# module.net
KiCad netlist of a schematic drawn in EAGLE
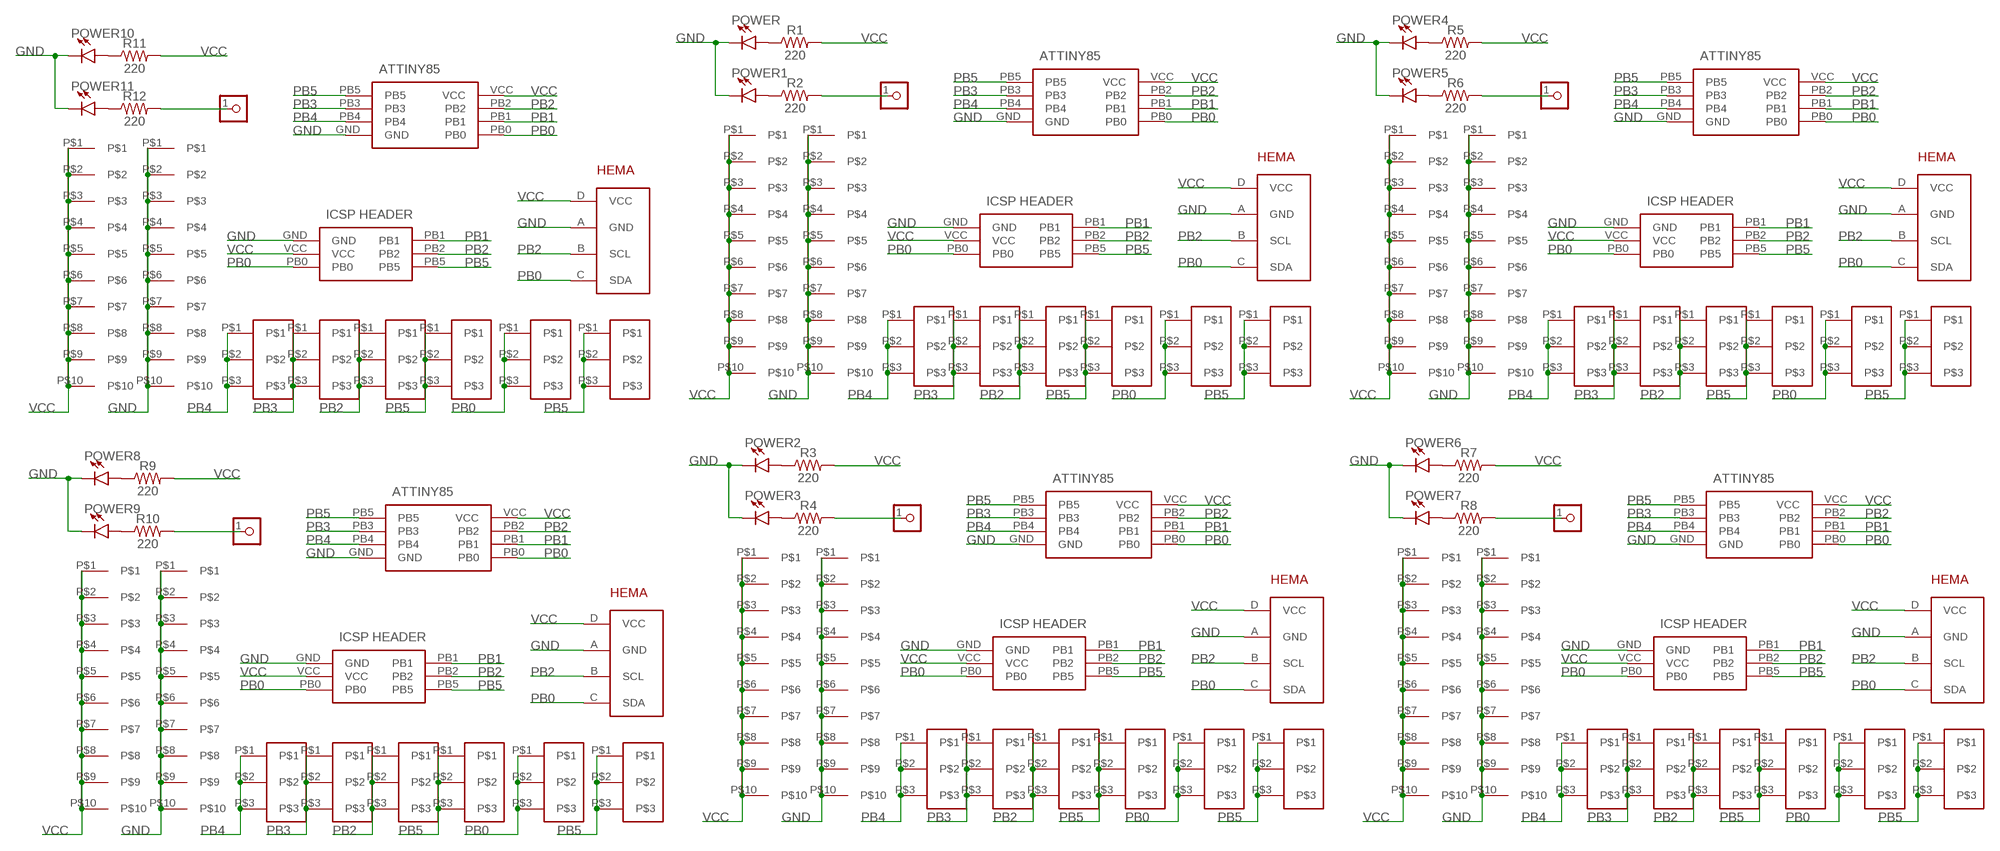
[diagram p0: schematic, sheet 1]

(export (version "E")
  (design (tool "Eeschema 10.0.6"))
  (components
    (comp (ref "0")
      (value "3X-PADS-CONNECTED")
      (footprint "eagle-import:3X-PADS")
      (libsource (lib "eagle-import") (part "3X-PADS-CONNECTED"))
    )
    (comp (ref "1")
      (value "3X-PADS-CONNECTED")
      (footprint "eagle-import:3X-PADS")
      (libsource (lib "eagle-import") (part "3X-PADS-CONNECTED"))
    )
    (comp (ref "2")
      (value "3X-PADS-CONNECTED")
      (footprint "eagle-import:3X-PADS")
      (libsource (lib "eagle-import") (part "3X-PADS-CONNECTED"))
    )
    (comp (ref "3")
      (value "3X-PADS-CONNECTED")
      (footprint "eagle-import:3X-PADS")
      (libsource (lib "eagle-import") (part "3X-PADS-CONNECTED"))
    )
    (comp (ref "4")
      (value "3X-PADS-CONNECTED")
      (footprint "eagle-import:3X-PADS")
      (libsource (lib "eagle-import") (part "3X-PADS-CONNECTED"))
    )
    (comp (ref "5")
      (value "3X-PADS-CONNECTED")
      (footprint "eagle-import:3X-PADS")
      (libsource (lib "eagle-import") (part "3X-PADS-CONNECTED"))
    )
    (comp (ref "6")
      (value "3X-PADS-CONNECTED")
      (footprint "eagle-import:3X-PADS")
      (libsource (lib "eagle-import") (part "3X-PADS-CONNECTED"))
    )
    (comp (ref "7")
      (value "3X-PADS-CONNECTED")
      (footprint "eagle-import:3X-PADS")
      (libsource (lib "eagle-import") (part "3X-PADS-CONNECTED"))
    )
    (comp (ref "8")
      (value "3X-PADS-CONNECTED")
      (footprint "eagle-import:3X-PADS")
      (libsource (lib "eagle-import") (part "3X-PADS-CONNECTED"))
    )
    (comp (ref "9")
      (value "3X-PADS-CONNECTED")
      (footprint "eagle-import:3X-PADS")
      (libsource (lib "eagle-import") (part "3X-PADS-CONNECTED"))
    )
    (comp (ref "10")
      (value "3X-PADS-CONNECTED")
      (footprint "eagle-import:3X-PADS")
      (libsource (lib "eagle-import") (part "3X-PADS-CONNECTED"))
    )
    (comp (ref "11")
      (value "3X-PADS-CONNECTED")
      (footprint "eagle-import:3X-PADS")
      (libsource (lib "eagle-import") (part "3X-PADS-CONNECTED"))
    )
    (comp (ref "12")
      (value "3X-PADS-CONNECTED")
      (footprint "eagle-import:3X-PADS")
      (libsource (lib "eagle-import") (part "3X-PADS-CONNECTED"))
    )
    (comp (ref "13")
      (value "3X-PADS-CONNECTED")
      (footprint "eagle-import:3X-PADS")
      (libsource (lib "eagle-import") (part "3X-PADS-CONNECTED"))
    )
    (comp (ref "14")
      (value "3X-PADS-CONNECTED")
      (footprint "eagle-import:3X-PADS")
      (libsource (lib "eagle-import") (part "3X-PADS-CONNECTED"))
    )
    (comp (ref "15")
      (value "3X-PADS-CONNECTED")
      (footprint "eagle-import:3X-PADS")
      (libsource (lib "eagle-import") (part "3X-PADS-CONNECTED"))
    )
    (comp (ref "16")
      (value "3X-PADS-CONNECTED")
      (footprint "eagle-import:3X-PADS")
      (libsource (lib "eagle-import") (part "3X-PADS-CONNECTED"))
    )
    (comp (ref "17")
      (value "3X-PADS-CONNECTED")
      (footprint "eagle-import:3X-PADS")
      (libsource (lib "eagle-import") (part "3X-PADS-CONNECTED"))
    )
    (comp (ref "18")
      (value "3X-PADS-CONNECTED")
      (footprint "eagle-import:3X-PADS")
      (libsource (lib "eagle-import") (part "3X-PADS-CONNECTED"))
    )
    (comp (ref "19")
      (value "3X-PADS-CONNECTED")
      (footprint "eagle-import:3X-PADS")
      (libsource (lib "eagle-import") (part "3X-PADS-CONNECTED"))
    )
    (comp (ref "20")
      (value "3X-PADS-CONNECTED")
      (footprint "eagle-import:3X-PADS")
      (libsource (lib "eagle-import") (part "3X-PADS-CONNECTED"))
    )
    (comp (ref "21")
      (value "3X-PADS-CONNECTED")
      (footprint "eagle-import:3X-PADS")
      (libsource (lib "eagle-import") (part "3X-PADS-CONNECTED"))
    )
    (comp (ref "22")
      (value "3X-PADS-CONNECTED")
      (footprint "eagle-import:3X-PADS")
      (libsource (lib "eagle-import") (part "3X-PADS-CONNECTED"))
    )
    (comp (ref "23")
      (value "3X-PADS-CONNECTED")
      (footprint "eagle-import:3X-PADS")
      (libsource (lib "eagle-import") (part "3X-PADS-CONNECTED"))
    )
    (comp (ref "24")
      (value "3X-PADS-CONNECTED")
      (footprint "eagle-import:3X-PADS")
      (libsource (lib "eagle-import") (part "3X-PADS-CONNECTED"))
    )
    (comp (ref "25")
      (value "3X-PADS-CONNECTED")
      (footprint "eagle-import:3X-PADS")
      (libsource (lib "eagle-import") (part "3X-PADS-CONNECTED"))
    )
    (comp (ref "26")
      (value "3X-PADS-CONNECTED")
      (footprint "eagle-import:3X-PADS")
      (libsource (lib "eagle-import") (part "3X-PADS-CONNECTED"))
    )
    (comp (ref "27")
      (value "3X-PADS-CONNECTED")
      (footprint "eagle-import:3X-PADS")
      (libsource (lib "eagle-import") (part "3X-PADS-CONNECTED"))
    )
    (comp (ref "28")
      (value "3X-PADS-CONNECTED")
      (footprint "eagle-import:3X-PADS")
      (libsource (lib "eagle-import") (part "3X-PADS-CONNECTED"))
    )
    (comp (ref "29")
      (value "3X-PADS-CONNECTED")
      (footprint "eagle-import:3X-PADS")
      (libsource (lib "eagle-import") (part "3X-PADS-CONNECTED"))
    )
    (comp (ref "30")
      (value "3X-PADS-CONNECTED")
      (footprint "eagle-import:3X-PADS")
      (libsource (lib "eagle-import") (part "3X-PADS-CONNECTED"))
    )
    (comp (ref "31")
      (value "3X-PADS-CONNECTED")
      (footprint "eagle-import:3X-PADS")
      (libsource (lib "eagle-import") (part "3X-PADS-CONNECTED"))
    )
    (comp (ref "32")
      (value "3X-PADS-CONNECTED")
      (footprint "eagle-import:3X-PADS")
      (libsource (lib "eagle-import") (part "3X-PADS-CONNECTED"))
    )
    (comp (ref "33")
      (value "3X-PADS-CONNECTED")
      (footprint "eagle-import:3X-PADS")
      (libsource (lib "eagle-import") (part "3X-PADS-CONNECTED"))
    )
    (comp (ref "34")
      (value "3X-PADS-CONNECTED")
      (footprint "eagle-import:3X-PADS")
      (libsource (lib "eagle-import") (part "3X-PADS-CONNECTED"))
    )
    (comp (ref "35")
      (value "3X-PADS-CONNECTED")
      (footprint "eagle-import:3X-PADS")
      (libsource (lib "eagle-import") (part "3X-PADS-CONNECTED"))
    )
    (comp (ref "GND")
      (value "10X-PADS")
      (footprint "eagle-import:10X-PADS")
      (libsource (lib "eagle-import") (part "10X-PADS"))
    )
    (comp (ref "GND1")
      (value "10X-PADS")
      (footprint "eagle-import:10X-PADS")
      (libsource (lib "eagle-import") (part "10X-PADS"))
    )
    (comp (ref "GND2")
      (value "10X-PADS")
      (footprint "eagle-import:10X-PADS")
      (libsource (lib "eagle-import") (part "10X-PADS"))
    )
    (comp (ref "GND3")
      (value "10X-PADS")
      (footprint "eagle-import:10X-PADS")
      (libsource (lib "eagle-import") (part "10X-PADS"))
    )
    (comp (ref "GND4")
      (value "10X-PADS")
      (footprint "eagle-import:10X-PADS")
      (libsource (lib "eagle-import") (part "10X-PADS"))
    )
    (comp (ref "GND5")
      (value "10X-PADS")
      (footprint "eagle-import:10X-PADS")
      (libsource (lib "eagle-import") (part "10X-PADS"))
    )
    (comp (ref "IC1")
      (value "ATTINY85-20SU")
      (footprint "eagle-import:SOT127P798X216-8N")
      (fields (field (name "RS_PART_NUMBER") "1331674"))
      (libsource (lib "eagle-import") (part "ATTINY85-20SU"))
    )
    (comp (ref "IC2")
      (value "ATTINY85-20SU")
      (footprint "eagle-import:SOT127P798X216-8N")
      (fields (field (name "RS_PART_NUMBER") "1331674"))
      (libsource (lib "eagle-import") (part "ATTINY85-20SU"))
    )
    (comp (ref "IC3")
      (value "ATTINY85-20SU")
      (footprint "eagle-import:SOT127P798X216-8N")
      (fields (field (name "RS_PART_NUMBER") "1331674"))
      (libsource (lib "eagle-import") (part "ATTINY85-20SU"))
    )
    (comp (ref "IC4")
      (value "ATTINY85-20SU")
      (footprint "eagle-import:SOT127P798X216-8N")
      (fields (field (name "RS_PART_NUMBER") "1331674"))
      (libsource (lib "eagle-import") (part "ATTINY85-20SU"))
    )
    (comp (ref "IC5")
      (value "ATTINY85-20SU")
      (footprint "eagle-import:SOT127P798X216-8N")
      (fields (field (name "RS_PART_NUMBER") "1331674"))
      (libsource (lib "eagle-import") (part "ATTINY85-20SU"))
    )
    (comp (ref "IC6")
      (value "ATTINY85-20SU")
      (footprint "eagle-import:SOT127P798X216-8N")
      (fields (field (name "RS_PART_NUMBER") "1331674"))
      (libsource (lib "eagle-import") (part "ATTINY85-20SU"))
    )
    (comp (ref "J1")
      (value "M20-9980346")
      (footprint "eagle-import:HDRV6W64P254_2X3_762X508X868P")
      (fields (field (name "RS_PART_NUMBER") "7457046P"))
      (libsource (lib "eagle-import") (part "M20-9980346"))
    )
    (comp (ref "J2")
      (value "M20-9980346")
      (footprint "eagle-import:HDRV6W64P254_2X3_762X508X868P")
      (fields (field (name "RS_PART_NUMBER") "7457046P"))
      (libsource (lib "eagle-import") (part "M20-9980346"))
    )
    (comp (ref "J3")
      (value "M20-9980346")
      (footprint "eagle-import:HDRV6W64P254_2X3_762X508X868P")
      (fields (field (name "RS_PART_NUMBER") "7457046P"))
      (libsource (lib "eagle-import") (part "M20-9980346"))
    )
    (comp (ref "J4")
      (value "M20-9980346")
      (footprint "eagle-import:HDRV6W64P254_2X3_762X508X868P")
      (fields (field (name "RS_PART_NUMBER") "7457046P"))
      (libsource (lib "eagle-import") (part "M20-9980346"))
    )
    (comp (ref "J5")
      (value "M20-9980346")
      (footprint "eagle-import:HDRV6W64P254_2X3_762X508X868P")
      (fields (field (name "RS_PART_NUMBER") "7457046P"))
      (libsource (lib "eagle-import") (part "M20-9980346"))
    )
    (comp (ref "J6")
      (value "M20-9980346")
      (footprint "eagle-import:HDRV6W64P254_2X3_762X508X868P")
      (fields (field (name "RS_PART_NUMBER") "7457046P"))
      (libsource (lib "eagle-import") (part "M20-9980346"))
    )
    (comp (ref "P1")
      (value "PROTO_VIAS_01X01-1.2")
      (footprint "eagle-import:PROTO_VIAS_01X01_1.2")
      (libsource (lib "eagle-import") (part "PROTO_VIAS_01X01-1.2"))
    )
    (comp (ref "P2")
      (value "PROTO_VIAS_01X01-1.2")
      (footprint "eagle-import:PROTO_VIAS_01X01_1.2")
      (libsource (lib "eagle-import") (part "PROTO_VIAS_01X01-1.2"))
    )
    (comp (ref "P3")
      (value "PROTO_VIAS_01X01-1.2")
      (footprint "eagle-import:PROTO_VIAS_01X01_1.2")
      (libsource (lib "eagle-import") (part "PROTO_VIAS_01X01-1.2"))
    )
    (comp (ref "P4")
      (value "PROTO_VIAS_01X01-1.2")
      (footprint "eagle-import:PROTO_VIAS_01X01_1.2")
      (libsource (lib "eagle-import") (part "PROTO_VIAS_01X01-1.2"))
    )
    (comp (ref "P5")
      (value "PROTO_VIAS_01X01-1.2")
      (footprint "eagle-import:PROTO_VIAS_01X01_1.2")
      (libsource (lib "eagle-import") (part "PROTO_VIAS_01X01-1.2"))
    )
    (comp (ref "P6")
      (value "PROTO_VIAS_01X01-1.2")
      (footprint "eagle-import:PROTO_VIAS_01X01_1.2")
      (libsource (lib "eagle-import") (part "PROTO_VIAS_01X01-1.2"))
    )
    (comp (ref "POWER")
      (value "LED3MM")
      (footprint "eagle-import:LED_3MM")
      (libsource (lib "eagle-import") (part "LED3MM"))
    )
    (comp (ref "POWER1")
      (value "LED3MM")
      (footprint "eagle-import:LED_3MM")
      (libsource (lib "eagle-import") (part "LED3MM"))
    )
    (comp (ref "POWER2")
      (value "LED3MM")
      (footprint "eagle-import:LED_3MM")
      (libsource (lib "eagle-import") (part "LED3MM"))
    )
    (comp (ref "POWER3")
      (value "LED3MM")
      (footprint "eagle-import:LED_3MM")
      (libsource (lib "eagle-import") (part "LED3MM"))
    )
    (comp (ref "POWER4")
      (value "LED3MM")
      (footprint "eagle-import:LED_3MM")
      (libsource (lib "eagle-import") (part "LED3MM"))
    )
    (comp (ref "POWER5")
      (value "LED3MM")
      (footprint "eagle-import:LED_3MM")
      (libsource (lib "eagle-import") (part "LED3MM"))
    )
    (comp (ref "POWER6")
      (value "LED3MM")
      (footprint "eagle-import:LED_3MM")
      (libsource (lib "eagle-import") (part "LED3MM"))
    )
    (comp (ref "POWER7")
      (value "LED3MM")
      (footprint "eagle-import:LED_3MM")
      (libsource (lib "eagle-import") (part "LED3MM"))
    )
    (comp (ref "POWER8")
      (value "LED3MM")
      (footprint "eagle-import:LED_3MM")
      (libsource (lib "eagle-import") (part "LED3MM"))
    )
    (comp (ref "POWER9")
      (value "LED3MM")
      (footprint "eagle-import:LED_3MM")
      (libsource (lib "eagle-import") (part "LED3MM"))
    )
    (comp (ref "POWER10")
      (value "LED3MM")
      (footprint "eagle-import:LED_3MM")
      (libsource (lib "eagle-import") (part "LED3MM"))
    )
    (comp (ref "POWER11")
      (value "LED3MM")
      (footprint "eagle-import:LED_3MM")
      (libsource (lib "eagle-import") (part "LED3MM"))
    )
    (comp (ref "R1")
      (value "220")
      (footprint "eagle-import:AXIAL-0.3")
      (libsource (lib "eagle-import") (part "RESISTORAXIAL-0.3"))
    )
    (comp (ref "R2")
      (value "220")
      (footprint "eagle-import:AXIAL-0.3")
      (libsource (lib "eagle-import") (part "RESISTORAXIAL-0.3"))
    )
    (comp (ref "R3")
      (value "220")
      (footprint "eagle-import:AXIAL-0.3")
      (libsource (lib "eagle-import") (part "RESISTORAXIAL-0.3"))
    )
    (comp (ref "R4")
      (value "220")
      (footprint "eagle-import:AXIAL-0.3")
      (libsource (lib "eagle-import") (part "RESISTORAXIAL-0.3"))
    )
    (comp (ref "R5")
      (value "220")
      (footprint "eagle-import:AXIAL-0.3")
      (libsource (lib "eagle-import") (part "RESISTORAXIAL-0.3"))
    )
    (comp (ref "R6")
      (value "220")
      (footprint "eagle-import:AXIAL-0.3")
      (libsource (lib "eagle-import") (part "RESISTORAXIAL-0.3"))
    )
    (comp (ref "R7")
      (value "220")
      (footprint "eagle-import:AXIAL-0.3")
      (libsource (lib "eagle-import") (part "RESISTORAXIAL-0.3"))
    )
    (comp (ref "R8")
      (value "220")
      (footprint "eagle-import:AXIAL-0.3")
      (libsource (lib "eagle-import") (part "RESISTORAXIAL-0.3"))
    )
    (comp (ref "R9")
      (value "220")
      (footprint "eagle-import:AXIAL-0.3")
      (libsource (lib "eagle-import") (part "RESISTORAXIAL-0.3"))
    )
    (comp (ref "R10")
      (value "220")
      (footprint "eagle-import:AXIAL-0.3")
      (libsource (lib "eagle-import") (part "RESISTORAXIAL-0.3"))
    )
    (comp (ref "R11")
      (value "220")
      (footprint "eagle-import:AXIAL-0.3")
      (libsource (lib "eagle-import") (part "RESISTORAXIAL-0.3"))
    )
    (comp (ref "R12")
      (value "220")
      (footprint "eagle-import:AXIAL-0.3")
      (libsource (lib "eagle-import") (part "RESISTORAXIAL-0.3"))
    )
    (comp (ref "U$1")
      (value "HEMA-I2C")
      (footprint "eagle-import:HEMA-I2C")
      (libsource (lib "eagle-import") (part "HEMA-I2C"))
    )
    (comp (ref "U$2")
      (value "HEMA-I2C")
      (footprint "eagle-import:HEMA-I2C")
      (libsource (lib "eagle-import") (part "HEMA-I2C"))
    )
    (comp (ref "U$3")
      (value "HEMA-I2C")
      (footprint "eagle-import:HEMA-I2C")
      (libsource (lib "eagle-import") (part "HEMA-I2C"))
    )
    (comp (ref "U$4")
      (value "HEMA-I2C")
      (footprint "eagle-import:HEMA-I2C")
      (libsource (lib "eagle-import") (part "HEMA-I2C"))
    )
    (comp (ref "U$5")
      (value "HEMA-I2C")
      (footprint "eagle-import:HEMA-I2C")
      (libsource (lib "eagle-import") (part "HEMA-I2C"))
    )
    (comp (ref "U$6")
      (value "HEMA-I2C")
      (footprint "eagle-import:HEMA-I2C")
      (libsource (lib "eagle-import") (part "HEMA-I2C"))
    )
    (comp (ref "VCC")
      (value "10X-PADS")
      (footprint "eagle-import:10X-PADS")
      (libsource (lib "eagle-import") (part "10X-PADS"))
    )
    (comp (ref "VCC1")
      (value "10X-PADS")
      (footprint "eagle-import:10X-PADS")
      (libsource (lib "eagle-import") (part "10X-PADS"))
    )
    (comp (ref "VCC2")
      (value "10X-PADS")
      (footprint "eagle-import:10X-PADS")
      (libsource (lib "eagle-import") (part "10X-PADS"))
    )
    (comp (ref "VCC3")
      (value "10X-PADS")
      (footprint "eagle-import:10X-PADS")
      (libsource (lib "eagle-import") (part "10X-PADS"))
    )
    (comp (ref "VCC4")
      (value "10X-PADS")
      (footprint "eagle-import:10X-PADS")
      (libsource (lib "eagle-import") (part "10X-PADS"))
    )
    (comp (ref "VCC5")
      (value "10X-PADS")
      (footprint "eagle-import:10X-PADS")
      (libsource (lib "eagle-import") (part "10X-PADS"))
    )
  )
  (nets
    (net (code "1") (name "/GND") (class "Default")
      (node (ref "GND") (pin "P$1") (pinfunction "P$1_P$1") (pintype "bidirectional"))
      (node (ref "GND") (pin "P$10") (pinfunction "P$10_P$10") (pintype "bidirectional"))
      (node (ref "GND") (pin "P$2") (pinfunction "P$2_P$2") (pintype "bidirectional"))
      (node (ref "GND") (pin "P$3") (pinfunction "P$3_P$3") (pintype "bidirectional"))
      (node (ref "GND") (pin "P$4") (pinfunction "P$4_P$4") (pintype "bidirectional"))
      (node (ref "GND") (pin "P$5") (pinfunction "P$5_P$5") (pintype "bidirectional"))
      (node (ref "GND") (pin "P$6") (pinfunction "P$6_P$6") (pintype "bidirectional"))
      (node (ref "GND") (pin "P$7") (pinfunction "P$7_P$7") (pintype "bidirectional"))
      (node (ref "GND") (pin "P$8") (pinfunction "P$8_P$8") (pintype "bidirectional"))
      (node (ref "GND") (pin "P$9") (pinfunction "P$9_P$9") (pintype "bidirectional"))
      (node (ref "GND1") (pin "P$1") (pinfunction "P$1_P$1") (pintype "bidirectional"))
      (node (ref "GND1") (pin "P$10") (pinfunction "P$10_P$10") (pintype "bidirectional"))
      (node (ref "GND1") (pin "P$2") (pinfunction "P$2_P$2") (pintype "bidirectional"))
      (node (ref "GND1") (pin "P$3") (pinfunction "P$3_P$3") (pintype "bidirectional"))
      (node (ref "GND1") (pin "P$4") (pinfunction "P$4_P$4") (pintype "bidirectional"))
      (node (ref "GND1") (pin "P$5") (pinfunction "P$5_P$5") (pintype "bidirectional"))
      (node (ref "GND1") (pin "P$6") (pinfunction "P$6_P$6") (pintype "bidirectional"))
      (node (ref "GND1") (pin "P$7") (pinfunction "P$7_P$7") (pintype "bidirectional"))
      (node (ref "GND1") (pin "P$8") (pinfunction "P$8_P$8") (pintype "bidirectional"))
      (node (ref "GND1") (pin "P$9") (pinfunction "P$9_P$9") (pintype "bidirectional"))
      (node (ref "GND2") (pin "P$1") (pinfunction "P$1_P$1") (pintype "bidirectional"))
      (node (ref "GND2") (pin "P$10") (pinfunction "P$10_P$10") (pintype "bidirectional"))
      (node (ref "GND2") (pin "P$2") (pinfunction "P$2_P$2") (pintype "bidirectional"))
      (node (ref "GND2") (pin "P$3") (pinfunction "P$3_P$3") (pintype "bidirectional"))
      (node (ref "GND2") (pin "P$4") (pinfunction "P$4_P$4") (pintype "bidirectional"))
      (node (ref "GND2") (pin "P$5") (pinfunction "P$5_P$5") (pintype "bidirectional"))
      (node (ref "GND2") (pin "P$6") (pinfunction "P$6_P$6") (pintype "bidirectional"))
      (node (ref "GND2") (pin "P$7") (pinfunction "P$7_P$7") (pintype "bidirectional"))
      (node (ref "GND2") (pin "P$8") (pinfunction "P$8_P$8") (pintype "bidirectional"))
      (node (ref "GND2") (pin "P$9") (pinfunction "P$9_P$9") (pintype "bidirectional"))
      (node (ref "GND3") (pin "P$1") (pinfunction "P$1_P$1") (pintype "bidirectional"))
      (node (ref "GND3") (pin "P$10") (pinfunction "P$10_P$10") (pintype "bidirectional"))
      (node (ref "GND3") (pin "P$2") (pinfunction "P$2_P$2") (pintype "bidirectional"))
      (node (ref "GND3") (pin "P$3") (pinfunction "P$3_P$3") (pintype "bidirectional"))
      (node (ref "GND3") (pin "P$4") (pinfunction "P$4_P$4") (pintype "bidirectional"))
      (node (ref "GND3") (pin "P$5") (pinfunction "P$5_P$5") (pintype "bidirectional"))
      (node (ref "GND3") (pin "P$6") (pinfunction "P$6_P$6") (pintype "bidirectional"))
      (node (ref "GND3") (pin "P$7") (pinfunction "P$7_P$7") (pintype "bidirectional"))
      (node (ref "GND3") (pin "P$8") (pinfunction "P$8_P$8") (pintype "bidirectional"))
      (node (ref "GND3") (pin "P$9") (pinfunction "P$9_P$9") (pintype "bidirectional"))
      (node (ref "GND4") (pin "P$1") (pinfunction "P$1_P$1") (pintype "bidirectional"))
      (node (ref "GND4") (pin "P$10") (pinfunction "P$10_P$10") (pintype "bidirectional"))
      (node (ref "GND4") (pin "P$2") (pinfunction "P$2_P$2") (pintype "bidirectional"))
      (node (ref "GND4") (pin "P$3") (pinfunction "P$3_P$3") (pintype "bidirectional"))
      (node (ref "GND4") (pin "P$4") (pinfunction "P$4_P$4") (pintype "bidirectional"))
      (node (ref "GND4") (pin "P$5") (pinfunction "P$5_P$5") (pintype "bidirectional"))
      (node (ref "GND4") (pin "P$6") (pinfunction "P$6_P$6") (pintype "bidirectional"))
      (node (ref "GND4") (pin "P$7") (pinfunction "P$7_P$7") (pintype "bidirectional"))
      (node (ref "GND4") (pin "P$8") (pinfunction "P$8_P$8") (pintype "bidirectional"))
      (node (ref "GND4") (pin "P$9") (pinfunction "P$9_P$9") (pintype "bidirectional"))
      (node (ref "GND5") (pin "P$1") (pinfunction "P$1_P$1") (pintype "bidirectional"))
      (node (ref "GND5") (pin "P$10") (pinfunction "P$10_P$10") (pintype "bidirectional"))
      (node (ref "GND5") (pin "P$2") (pinfunction "P$2_P$2") (pintype "bidirectional"))
      (node (ref "GND5") (pin "P$3") (pinfunction "P$3_P$3") (pintype "bidirectional"))
      (node (ref "GND5") (pin "P$4") (pinfunction "P$4_P$4") (pintype "bidirectional"))
      (node (ref "GND5") (pin "P$5") (pinfunction "P$5_P$5") (pintype "bidirectional"))
      (node (ref "GND5") (pin "P$6") (pinfunction "P$6_P$6") (pintype "bidirectional"))
      (node (ref "GND5") (pin "P$7") (pinfunction "P$7_P$7") (pintype "bidirectional"))
      (node (ref "GND5") (pin "P$8") (pinfunction "P$8_P$8") (pintype "bidirectional"))
      (node (ref "GND5") (pin "P$9") (pinfunction "P$9_P$9") (pintype "bidirectional"))
      (node (ref "IC1") (pin "GND") (pinfunction "GND_GND") (pintype "bidirectional"))
      (node (ref "IC2") (pin "GND") (pinfunction "GND_GND") (pintype "bidirectional"))
      (node (ref "IC3") (pin "GND") (pinfunction "GND_GND") (pintype "bidirectional"))
      (node (ref "IC4") (pin "GND") (pinfunction "GND_GND") (pintype "bidirectional"))
      (node (ref "IC5") (pin "GND") (pinfunction "GND_GND") (pintype "bidirectional"))
      (node (ref "IC6") (pin "GND") (pinfunction "GND_GND") (pintype "bidirectional"))
      (node (ref "J1") (pin "GND") (pinfunction "GND_GND") (pintype "bidirectional"))
      (node (ref "J2") (pin "GND") (pinfunction "GND_GND") (pintype "bidirectional"))
      (node (ref "J3") (pin "GND") (pinfunction "GND_GND") (pintype "bidirectional"))
      (node (ref "J4") (pin "GND") (pinfunction "GND_GND") (pintype "bidirectional"))
      (node (ref "J5") (pin "GND") (pinfunction "GND_GND") (pintype "bidirectional"))
      (node (ref "J6") (pin "GND") (pinfunction "GND_GND") (pintype "bidirectional"))
      (node (ref "POWER") (pin "K") (pinfunction "C_K") (pintype "passive"))
      (node (ref "POWER1") (pin "K") (pinfunction "C_K") (pintype "passive"))
      (node (ref "POWER10") (pin "K") (pinfunction "C_K") (pintype "passive"))
      (node (ref "POWER11") (pin "K") (pinfunction "C_K") (pintype "passive"))
      (node (ref "POWER2") (pin "K") (pinfunction "C_K") (pintype "passive"))
      (node (ref "POWER3") (pin "K") (pinfunction "C_K") (pintype "passive"))
      (node (ref "POWER4") (pin "K") (pinfunction "C_K") (pintype "passive"))
      (node (ref "POWER5") (pin "K") (pinfunction "C_K") (pintype "passive"))
      (node (ref "POWER6") (pin "K") (pinfunction "C_K") (pintype "passive"))
      (node (ref "POWER7") (pin "K") (pinfunction "C_K") (pintype "passive"))
      (node (ref "POWER8") (pin "K") (pinfunction "C_K") (pintype "passive"))
      (node (ref "POWER9") (pin "K") (pinfunction "C_K") (pintype "passive"))
      (node (ref "U$1") (pin "A") (pinfunction "GND_A") (pintype "bidirectional"))
      (node (ref "U$2") (pin "A") (pinfunction "GND_A") (pintype "bidirectional"))
      (node (ref "U$3") (pin "A") (pinfunction "GND_A") (pintype "bidirectional"))
      (node (ref "U$4") (pin "A") (pinfunction "GND_A") (pintype "bidirectional"))
      (node (ref "U$5") (pin "A") (pinfunction "GND_A") (pintype "bidirectional"))
      (node (ref "U$6") (pin "A") (pinfunction "GND_A") (pintype "bidirectional"))
    )
    (net (code "2") (name "/PB0") (class "Default")
      (node (ref "0") (pin "P$1") (pinfunction "P$1_P$1") (pintype "bidirectional"))
      (node (ref "0") (pin "P$2") (pinfunction "P$2_P$2") (pintype "bidirectional"))
      (node (ref "0") (pin "P$3") (pinfunction "P$3_P$3") (pintype "bidirectional"))
      (node (ref "10") (pin "P$1") (pinfunction "P$1_P$1") (pintype "bidirectional"))
      (node (ref "10") (pin "P$2") (pinfunction "P$2_P$2") (pintype "bidirectional"))
      (node (ref "10") (pin "P$3") (pinfunction "P$3_P$3") (pintype "bidirectional"))
      (node (ref "16") (pin "P$1") (pinfunction "P$1_P$1") (pintype "bidirectional"))
      (node (ref "16") (pin "P$2") (pinfunction "P$2_P$2") (pintype "bidirectional"))
      (node (ref "16") (pin "P$3") (pinfunction "P$3_P$3") (pintype "bidirectional"))
      (node (ref "22") (pin "P$1") (pinfunction "P$1_P$1") (pintype "bidirectional"))
      (node (ref "22") (pin "P$2") (pinfunction "P$2_P$2") (pintype "bidirectional"))
      (node (ref "22") (pin "P$3") (pinfunction "P$3_P$3") (pintype "bidirectional"))
      (node (ref "28") (pin "P$1") (pinfunction "P$1_P$1") (pintype "bidirectional"))
      (node (ref "28") (pin "P$2") (pinfunction "P$2_P$2") (pintype "bidirectional"))
      (node (ref "28") (pin "P$3") (pinfunction "P$3_P$3") (pintype "bidirectional"))
      (node (ref "34") (pin "P$1") (pinfunction "P$1_P$1") (pintype "bidirectional"))
      (node (ref "34") (pin "P$2") (pinfunction "P$2_P$2") (pintype "bidirectional"))
      (node (ref "34") (pin "P$3") (pinfunction "P$3_P$3") (pintype "bidirectional"))
      (node (ref "IC1") (pin "PB0") (pinfunction "PB0_PB0") (pintype "bidirectional"))
      (node (ref "IC2") (pin "PB0") (pinfunction "PB0_PB0") (pintype "bidirectional"))
      (node (ref "IC3") (pin "PB0") (pinfunction "PB0_PB0") (pintype "bidirectional"))
      (node (ref "IC4") (pin "PB0") (pinfunction "PB0_PB0") (pintype "bidirectional"))
      (node (ref "IC5") (pin "PB0") (pinfunction "PB0_PB0") (pintype "bidirectional"))
      (node (ref "IC6") (pin "PB0") (pinfunction "PB0_PB0") (pintype "bidirectional"))
      (node (ref "J1") (pin "PB0") (pinfunction "PB0_PB0") (pintype "bidirectional"))
      (node (ref "J2") (pin "PB0") (pinfunction "PB0_PB0") (pintype "bidirectional"))
      (node (ref "J3") (pin "PB0") (pinfunction "PB0_PB0") (pintype "bidirectional"))
      (node (ref "J4") (pin "PB0") (pinfunction "PB0_PB0") (pintype "bidirectional"))
      (node (ref "J5") (pin "PB0") (pinfunction "PB0_PB0") (pintype "bidirectional"))
      (node (ref "J6") (pin "PB0") (pinfunction "PB0_PB0") (pintype "bidirectional"))
      (node (ref "U$1") (pin "C") (pinfunction "SDA_C") (pintype "bidirectional"))
      (node (ref "U$2") (pin "C") (pinfunction "SDA_C") (pintype "bidirectional"))
      (node (ref "U$3") (pin "C") (pinfunction "SDA_C") (pintype "bidirectional"))
      (node (ref "U$4") (pin "C") (pinfunction "SDA_C") (pintype "bidirectional"))
      (node (ref "U$5") (pin "C") (pinfunction "SDA_C") (pintype "bidirectional"))
      (node (ref "U$6") (pin "C") (pinfunction "SDA_C") (pintype "bidirectional"))
    )
    (net (code "3") (name "/PB1") (class "Default")
      (node (ref "IC1") (pin "PB1") (pinfunction "PB1_PB1") (pintype "bidirectional"))
      (node (ref "IC2") (pin "PB1") (pinfunction "PB1_PB1") (pintype "bidirectional"))
      (node (ref "IC3") (pin "PB1") (pinfunction "PB1_PB1") (pintype "bidirectional"))
      (node (ref "IC4") (pin "PB1") (pinfunction "PB1_PB1") (pintype "bidirectional"))
      (node (ref "IC5") (pin "PB1") (pinfunction "PB1_PB1") (pintype "bidirectional"))
      (node (ref "IC6") (pin "PB1") (pinfunction "PB1_PB1") (pintype "bidirectional"))
      (node (ref "J1") (pin "PB1") (pinfunction "PB1_PB1") (pintype "bidirectional"))
      (node (ref "J2") (pin "PB1") (pinfunction "PB1_PB1") (pintype "bidirectional"))
      (node (ref "J3") (pin "PB1") (pinfunction "PB1_PB1") (pintype "bidirectional"))
      (node (ref "J4") (pin "PB1") (pinfunction "PB1_PB1") (pintype "bidirectional"))
      (node (ref "J5") (pin "PB1") (pinfunction "PB1_PB1") (pintype "bidirectional"))
      (node (ref "J6") (pin "PB1") (pinfunction "PB1_PB1") (pintype "bidirectional"))
    )
    (net (code "4") (name "/PB2") (class "Default")
      (node (ref "14") (pin "P$1") (pinfunction "P$1_P$1") (pintype "bidirectional"))
      (node (ref "14") (pin "P$2") (pinfunction "P$2_P$2") (pintype "bidirectional"))
      (node (ref "14") (pin "P$3") (pinfunction "P$3_P$3") (pintype "bidirectional"))
      (node (ref "2") (pin "P$1") (pinfunction "P$1_P$1") (pintype "bidirectional"))
      (node (ref "2") (pin "P$2") (pinfunction "P$2_P$2") (pintype "bidirectional"))
      (node (ref "2") (pin "P$3") (pinfunction "P$3_P$3") (pintype "bidirectional"))
      (node (ref "20") (pin "P$1") (pinfunction "P$1_P$1") (pintype "bidirectional"))
      (node (ref "20") (pin "P$2") (pinfunction "P$2_P$2") (pintype "bidirectional"))
      (node (ref "20") (pin "P$3") (pinfunction "P$3_P$3") (pintype "bidirectional"))
      (node (ref "26") (pin "P$1") (pinfunction "P$1_P$1") (pintype "bidirectional"))
      (node (ref "26") (pin "P$2") (pinfunction "P$2_P$2") (pintype "bidirectional"))
      (node (ref "26") (pin "P$3") (pinfunction "P$3_P$3") (pintype "bidirectional"))
      (node (ref "32") (pin "P$1") (pinfunction "P$1_P$1") (pintype "bidirectional"))
      (node (ref "32") (pin "P$2") (pinfunction "P$2_P$2") (pintype "bidirectional"))
      (node (ref "32") (pin "P$3") (pinfunction "P$3_P$3") (pintype "bidirectional"))
      (node (ref "8") (pin "P$1") (pinfunction "P$1_P$1") (pintype "bidirectional"))
      (node (ref "8") (pin "P$2") (pinfunction "P$2_P$2") (pintype "bidirectional"))
      (node (ref "8") (pin "P$3") (pinfunction "P$3_P$3") (pintype "bidirectional"))
      (node (ref "IC1") (pin "PB2") (pinfunction "PB2_PB2") (pintype "bidirectional"))
      (node (ref "IC2") (pin "PB2") (pinfunction "PB2_PB2") (pintype "bidirectional"))
      (node (ref "IC3") (pin "PB2") (pinfunction "PB2_PB2") (pintype "bidirectional"))
      (node (ref "IC4") (pin "PB2") (pinfunction "PB2_PB2") (pintype "bidirectional"))
      (node (ref "IC5") (pin "PB2") (pinfunction "PB2_PB2") (pintype "bidirectional"))
      (node (ref "IC6") (pin "PB2") (pinfunction "PB2_PB2") (pintype "bidirectional"))
      (node (ref "J1") (pin "PB2") (pinfunction "PB2_PB2") (pintype "bidirectional"))
      (node (ref "J2") (pin "PB2") (pinfunction "PB2_PB2") (pintype "bidirectional"))
      (node (ref "J3") (pin "PB2") (pinfunction "PB2_PB2") (pintype "bidirectional"))
      (node (ref "J4") (pin "PB2") (pinfunction "PB2_PB2") (pintype "bidirectional"))
      (node (ref "J5") (pin "PB2") (pinfunction "PB2_PB2") (pintype "bidirectional"))
      (node (ref "J6") (pin "PB2") (pinfunction "PB2_PB2") (pintype "bidirectional"))
      (node (ref "U$1") (pin "B") (pinfunction "SCL_B") (pintype "bidirectional"))
      (node (ref "U$2") (pin "B") (pinfunction "SCL_B") (pintype "bidirectional"))
      (node (ref "U$3") (pin "B") (pinfunction "SCL_B") (pintype "bidirectional"))
      (node (ref "U$4") (pin "B") (pinfunction "SCL_B") (pintype "bidirectional"))
      (node (ref "U$5") (pin "B") (pinfunction "SCL_B") (pintype "bidirectional"))
      (node (ref "U$6") (pin "B") (pinfunction "SCL_B") (pintype "bidirectional"))
    )
    (net (code "5") (name "/PB3") (class "Default")
      (node (ref "13") (pin "P$1") (pinfunction "P$1_P$1") (pintype "bidirectional"))
      (node (ref "13") (pin "P$2") (pinfunction "P$2_P$2") (pintype "bidirectional"))
      (node (ref "13") (pin "P$3") (pinfunction "P$3_P$3") (pintype "bidirectional"))
      (node (ref "19") (pin "P$1") (pinfunction "P$1_P$1") (pintype "bidirectional"))
      (node (ref "19") (pin "P$2") (pinfunction "P$2_P$2") (pintype "bidirectional"))
      (node (ref "19") (pin "P$3") (pinfunction "P$3_P$3") (pintype "bidirectional"))
      (node (ref "25") (pin "P$1") (pinfunction "P$1_P$1") (pintype "bidirectional"))
      (node (ref "25") (pin "P$2") (pinfunction "P$2_P$2") (pintype "bidirectional"))
      (node (ref "25") (pin "P$3") (pinfunction "P$3_P$3") (pintype "bidirectional"))
      (node (ref "3") (pin "P$1") (pinfunction "P$1_P$1") (pintype "bidirectional"))
      (node (ref "3") (pin "P$2") (pinfunction "P$2_P$2") (pintype "bidirectional"))
      (node (ref "3") (pin "P$3") (pinfunction "P$3_P$3") (pintype "bidirectional"))
      (node (ref "31") (pin "P$1") (pinfunction "P$1_P$1") (pintype "bidirectional"))
      (node (ref "31") (pin "P$2") (pinfunction "P$2_P$2") (pintype "bidirectional"))
      (node (ref "31") (pin "P$3") (pinfunction "P$3_P$3") (pintype "bidirectional"))
      (node (ref "7") (pin "P$1") (pinfunction "P$1_P$1") (pintype "bidirectional"))
      (node (ref "7") (pin "P$2") (pinfunction "P$2_P$2") (pintype "bidirectional"))
      (node (ref "7") (pin "P$3") (pinfunction "P$3_P$3") (pintype "bidirectional"))
      (node (ref "IC1") (pin "PB3") (pinfunction "PB3_PB3") (pintype "bidirectional"))
      (node (ref "IC2") (pin "PB3") (pinfunction "PB3_PB3") (pintype "bidirectional"))
      (node (ref "IC3") (pin "PB3") (pinfunction "PB3_PB3") (pintype "bidirectional"))
      (node (ref "IC4") (pin "PB3") (pinfunction "PB3_PB3") (pintype "bidirectional"))
      (node (ref "IC5") (pin "PB3") (pinfunction "PB3_PB3") (pintype "bidirectional"))
      (node (ref "IC6") (pin "PB3") (pinfunction "PB3_PB3") (pintype "bidirectional"))
    )
    (net (code "6") (name "/PB4") (class "Default")
      (node (ref "12") (pin "P$1") (pinfunction "P$1_P$1") (pintype "bidirectional"))
      (node (ref "12") (pin "P$2") (pinfunction "P$2_P$2") (pintype "bidirectional"))
      (node (ref "12") (pin "P$3") (pinfunction "P$3_P$3") (pintype "bidirectional"))
      (node (ref "18") (pin "P$1") (pinfunction "P$1_P$1") (pintype "bidirectional"))
      (node (ref "18") (pin "P$2") (pinfunction "P$2_P$2") (pintype "bidirectional"))
      (node (ref "18") (pin "P$3") (pinfunction "P$3_P$3") (pintype "bidirectional"))
      (node (ref "24") (pin "P$1") (pinfunction "P$1_P$1") (pintype "bidirectional"))
      (node (ref "24") (pin "P$2") (pinfunction "P$2_P$2") (pintype "bidirectional"))
      (node (ref "24") (pin "P$3") (pinfunction "P$3_P$3") (pintype "bidirectional"))
      (node (ref "30") (pin "P$1") (pinfunction "P$1_P$1") (pintype "bidirectional"))
      (node (ref "30") (pin "P$2") (pinfunction "P$2_P$2") (pintype "bidirectional"))
      (node (ref "30") (pin "P$3") (pinfunction "P$3_P$3") (pintype "bidirectional"))
      (node (ref "4") (pin "P$1") (pinfunction "P$1_P$1") (pintype "bidirectional"))
      (node (ref "4") (pin "P$2") (pinfunction "P$2_P$2") (pintype "bidirectional"))
      (node (ref "4") (pin "P$3") (pinfunction "P$3_P$3") (pintype "bidirectional"))
      (node (ref "6") (pin "P$1") (pinfunction "P$1_P$1") (pintype "bidirectional"))
      (node (ref "6") (pin "P$2") (pinfunction "P$2_P$2") (pintype "bidirectional"))
      (node (ref "6") (pin "P$3") (pinfunction "P$3_P$3") (pintype "bidirectional"))
      (node (ref "IC1") (pin "PB4") (pinfunction "PB4_PB4") (pintype "bidirectional"))
      (node (ref "IC2") (pin "PB4") (pinfunction "PB4_PB4") (pintype "bidirectional"))
      (node (ref "IC3") (pin "PB4") (pinfunction "PB4_PB4") (pintype "bidirectional"))
      (node (ref "IC4") (pin "PB4") (pinfunction "PB4_PB4") (pintype "bidirectional"))
      (node (ref "IC5") (pin "PB4") (pinfunction "PB4_PB4") (pintype "bidirectional"))
      (node (ref "IC6") (pin "PB4") (pinfunction "PB4_PB4") (pintype "bidirectional"))
    )
    (net (code "7") (name "/PB5") (class "Default")
      (node (ref "1") (pin "P$1") (pinfunction "P$1_P$1") (pintype "bidirectional"))
      (node (ref "1") (pin "P$2") (pinfunction "P$2_P$2") (pintype "bidirectional"))
      (node (ref "1") (pin "P$3") (pinfunction "P$3_P$3") (pintype "bidirectional"))
      (node (ref "11") (pin "P$1") (pinfunction "P$1_P$1") (pintype "bidirectional"))
      (node (ref "11") (pin "P$2") (pinfunction "P$2_P$2") (pintype "bidirectional"))
      (node (ref "11") (pin "P$3") (pinfunction "P$3_P$3") (pintype "bidirectional"))
      (node (ref "15") (pin "P$1") (pinfunction "P$1_P$1") (pintype "bidirectional"))
      (node (ref "15") (pin "P$2") (pinfunction "P$2_P$2") (pintype "bidirectional"))
      (node (ref "15") (pin "P$3") (pinfunction "P$3_P$3") (pintype "bidirectional"))
      (node (ref "17") (pin "P$1") (pinfunction "P$1_P$1") (pintype "bidirectional"))
      (node (ref "17") (pin "P$2") (pinfunction "P$2_P$2") (pintype "bidirectional"))
      (node (ref "17") (pin "P$3") (pinfunction "P$3_P$3") (pintype "bidirectional"))
      (node (ref "21") (pin "P$1") (pinfunction "P$1_P$1") (pintype "bidirectional"))
      (node (ref "21") (pin "P$2") (pinfunction "P$2_P$2") (pintype "bidirectional"))
      (node (ref "21") (pin "P$3") (pinfunction "P$3_P$3") (pintype "bidirectional"))
      (node (ref "23") (pin "P$1") (pinfunction "P$1_P$1") (pintype "bidirectional"))
      (node (ref "23") (pin "P$2") (pinfunction "P$2_P$2") (pintype "bidirectional"))
      (node (ref "23") (pin "P$3") (pinfunction "P$3_P$3") (pintype "bidirectional"))
      (node (ref "27") (pin "P$1") (pinfunction "P$1_P$1") (pintype "bidirectional"))
      (node (ref "27") (pin "P$2") (pinfunction "P$2_P$2") (pintype "bidirectional"))
      (node (ref "27") (pin "P$3") (pinfunction "P$3_P$3") (pintype "bidirectional"))
      (node (ref "29") (pin "P$1") (pinfunction "P$1_P$1") (pintype "bidirectional"))
      (node (ref "29") (pin "P$2") (pinfunction "P$2_P$2") (pintype "bidirectional"))
      (node (ref "29") (pin "P$3") (pinfunction "P$3_P$3") (pintype "bidirectional"))
      (node (ref "33") (pin "P$1") (pinfunction "P$1_P$1") (pintype "bidirectional"))
      (node (ref "33") (pin "P$2") (pinfunction "P$2_P$2") (pintype "bidirectional"))
      (node (ref "33") (pin "P$3") (pinfunction "P$3_P$3") (pintype "bidirectional"))
      (node (ref "35") (pin "P$1") (pinfunction "P$1_P$1") (pintype "bidirectional"))
      (node (ref "35") (pin "P$2") (pinfunction "P$2_P$2") (pintype "bidirectional"))
      (node (ref "35") (pin "P$3") (pinfunction "P$3_P$3") (pintype "bidirectional"))
      (node (ref "5") (pin "P$1") (pinfunction "P$1_P$1") (pintype "bidirectional"))
      (node (ref "5") (pin "P$2") (pinfunction "P$2_P$2") (pintype "bidirectional"))
      (node (ref "5") (pin "P$3") (pinfunction "P$3_P$3") (pintype "bidirectional"))
      (node (ref "9") (pin "P$1") (pinfunction "P$1_P$1") (pintype "bidirectional"))
      (node (ref "9") (pin "P$2") (pinfunction "P$2_P$2") (pintype "bidirectional"))
      (node (ref "9") (pin "P$3") (pinfunction "P$3_P$3") (pintype "bidirectional"))
      (node (ref "IC1") (pin "PB5") (pinfunction "PB5_PB5") (pintype "bidirectional"))
      (node (ref "IC2") (pin "PB5") (pinfunction "PB5_PB5") (pintype "bidirectional"))
      (node (ref "IC3") (pin "PB5") (pinfunction "PB5_PB5") (pintype "bidirectional"))
      (node (ref "IC4") (pin "PB5") (pinfunction "PB5_PB5") (pintype "bidirectional"))
      (node (ref "IC5") (pin "PB5") (pinfunction "PB5_PB5") (pintype "bidirectional"))
      (node (ref "IC6") (pin "PB5") (pinfunction "PB5_PB5") (pintype "bidirectional"))
      (node (ref "J1") (pin "PB5") (pinfunction "PB5_PB5") (pintype "bidirectional"))
      (node (ref "J2") (pin "PB5") (pinfunction "PB5_PB5") (pintype "bidirectional"))
      (node (ref "J3") (pin "PB5") (pinfunction "PB5_PB5") (pintype "bidirectional"))
      (node (ref "J4") (pin "PB5") (pinfunction "PB5_PB5") (pintype "bidirectional"))
      (node (ref "J5") (pin "PB5") (pinfunction "PB5_PB5") (pintype "bidirectional"))
      (node (ref "J6") (pin "PB5") (pinfunction "PB5_PB5") (pintype "bidirectional"))
    )
    (net (code "8") (name "/VCC") (class "Default")
      (node (ref "IC1") (pin "VCC") (pinfunction "VCC_VCC") (pintype "bidirectional"))
      (node (ref "IC2") (pin "VCC") (pinfunction "VCC_VCC") (pintype "bidirectional"))
      (node (ref "IC3") (pin "VCC") (pinfunction "VCC_VCC") (pintype "bidirectional"))
      (node (ref "IC4") (pin "VCC") (pinfunction "VCC_VCC") (pintype "bidirectional"))
      (node (ref "IC5") (pin "VCC") (pinfunction "VCC_VCC") (pintype "bidirectional"))
      (node (ref "IC6") (pin "VCC") (pinfunction "VCC_VCC") (pintype "bidirectional"))
      (node (ref "J1") (pin "VCC") (pinfunction "VCC_VCC") (pintype "bidirectional"))
      (node (ref "J2") (pin "VCC") (pinfunction "VCC_VCC") (pintype "bidirectional"))
      (node (ref "J3") (pin "VCC") (pinfunction "VCC_VCC") (pintype "bidirectional"))
      (node (ref "J4") (pin "VCC") (pinfunction "VCC_VCC") (pintype "bidirectional"))
      (node (ref "J5") (pin "VCC") (pinfunction "VCC_VCC") (pintype "bidirectional"))
      (node (ref "J6") (pin "VCC") (pinfunction "VCC_VCC") (pintype "bidirectional"))
      (node (ref "R1") (pin "P$2") (pinfunction "2_P$2") (pintype "passive"))
      (node (ref "R11") (pin "P$2") (pinfunction "2_P$2") (pintype "passive"))
      (node (ref "R3") (pin "P$2") (pinfunction "2_P$2") (pintype "passive"))
      (node (ref "R5") (pin "P$2") (pinfunction "2_P$2") (pintype "passive"))
      (node (ref "R7") (pin "P$2") (pinfunction "2_P$2") (pintype "passive"))
      (node (ref "R9") (pin "P$2") (pinfunction "2_P$2") (pintype "passive"))
      (node (ref "U$1") (pin "D") (pinfunction "VCC_D") (pintype "bidirectional"))
      (node (ref "U$2") (pin "D") (pinfunction "VCC_D") (pintype "bidirectional"))
      (node (ref "U$3") (pin "D") (pinfunction "VCC_D") (pintype "bidirectional"))
      (node (ref "U$4") (pin "D") (pinfunction "VCC_D") (pintype "bidirectional"))
      (node (ref "U$5") (pin "D") (pinfunction "VCC_D") (pintype "bidirectional"))
      (node (ref "U$6") (pin "D") (pinfunction "VCC_D") (pintype "bidirectional"))
      (node (ref "VCC") (pin "P$1") (pinfunction "P$1_P$1") (pintype "bidirectional"))
      (node (ref "VCC") (pin "P$10") (pinfunction "P$10_P$10") (pintype "bidirectional"))
      (node (ref "VCC") (pin "P$2") (pinfunction "P$2_P$2") (pintype "bidirectional"))
      (node (ref "VCC") (pin "P$3") (pinfunction "P$3_P$3") (pintype "bidirectional"))
      (node (ref "VCC") (pin "P$4") (pinfunction "P$4_P$4") (pintype "bidirectional"))
      (node (ref "VCC") (pin "P$5") (pinfunction "P$5_P$5") (pintype "bidirectional"))
      (node (ref "VCC") (pin "P$6") (pinfunction "P$6_P$6") (pintype "bidirectional"))
      (node (ref "VCC") (pin "P$7") (pinfunction "P$7_P$7") (pintype "bidirectional"))
      (node (ref "VCC") (pin "P$8") (pinfunction "P$8_P$8") (pintype "bidirectional"))
      (node (ref "VCC") (pin "P$9") (pinfunction "P$9_P$9") (pintype "bidirectional"))
      (node (ref "VCC1") (pin "P$1") (pinfunction "P$1_P$1") (pintype "bidirectional"))
      (node (ref "VCC1") (pin "P$10") (pinfunction "P$10_P$10") (pintype "bidirectional"))
      (node (ref "VCC1") (pin "P$2") (pinfunction "P$2_P$2") (pintype "bidirectional"))
      (node (ref "VCC1") (pin "P$3") (pinfunction "P$3_P$3") (pintype "bidirectional"))
      (node (ref "VCC1") (pin "P$4") (pinfunction "P$4_P$4") (pintype "bidirectional"))
      (node (ref "VCC1") (pin "P$5") (pinfunction "P$5_P$5") (pintype "bidirectional"))
      (node (ref "VCC1") (pin "P$6") (pinfunction "P$6_P$6") (pintype "bidirectional"))
      (node (ref "VCC1") (pin "P$7") (pinfunction "P$7_P$7") (pintype "bidirectional"))
      (node (ref "VCC1") (pin "P$8") (pinfunction "P$8_P$8") (pintype "bidirectional"))
      (node (ref "VCC1") (pin "P$9") (pinfunction "P$9_P$9") (pintype "bidirectional"))
      (node (ref "VCC2") (pin "P$1") (pinfunction "P$1_P$1") (pintype "bidirectional"))
      (node (ref "VCC2") (pin "P$10") (pinfunction "P$10_P$10") (pintype "bidirectional"))
      (node (ref "VCC2") (pin "P$2") (pinfunction "P$2_P$2") (pintype "bidirectional"))
      (node (ref "VCC2") (pin "P$3") (pinfunction "P$3_P$3") (pintype "bidirectional"))
      (node (ref "VCC2") (pin "P$4") (pinfunction "P$4_P$4") (pintype "bidirectional"))
      (node (ref "VCC2") (pin "P$5") (pinfunction "P$5_P$5") (pintype "bidirectional"))
      (node (ref "VCC2") (pin "P$6") (pinfunction "P$6_P$6") (pintype "bidirectional"))
      (node (ref "VCC2") (pin "P$7") (pinfunction "P$7_P$7") (pintype "bidirectional"))
      (node (ref "VCC2") (pin "P$8") (pinfunction "P$8_P$8") (pintype "bidirectional"))
      (node (ref "VCC2") (pin "P$9") (pinfunction "P$9_P$9") (pintype "bidirectional"))
      (node (ref "VCC3") (pin "P$1") (pinfunction "P$1_P$1") (pintype "bidirectional"))
      (node (ref "VCC3") (pin "P$10") (pinfunction "P$10_P$10") (pintype "bidirectional"))
      (node (ref "VCC3") (pin "P$2") (pinfunction "P$2_P$2") (pintype "bidirectional"))
      (node (ref "VCC3") (pin "P$3") (pinfunction "P$3_P$3") (pintype "bidirectional"))
      (node (ref "VCC3") (pin "P$4") (pinfunction "P$4_P$4") (pintype "bidirectional"))
      (node (ref "VCC3") (pin "P$5") (pinfunction "P$5_P$5") (pintype "bidirectional"))
      (node (ref "VCC3") (pin "P$6") (pinfunction "P$6_P$6") (pintype "bidirectional"))
      (node (ref "VCC3") (pin "P$7") (pinfunction "P$7_P$7") (pintype "bidirectional"))
      (node (ref "VCC3") (pin "P$8") (pinfunction "P$8_P$8") (pintype "bidirectional"))
      (node (ref "VCC3") (pin "P$9") (pinfunction "P$9_P$9") (pintype "bidirectional"))
      (node (ref "VCC4") (pin "P$1") (pinfunction "P$1_P$1") (pintype "bidirectional"))
      (node (ref "VCC4") (pin "P$10") (pinfunction "P$10_P$10") (pintype "bidirectional"))
      (node (ref "VCC4") (pin "P$2") (pinfunction "P$2_P$2") (pintype "bidirectional"))
      (node (ref "VCC4") (pin "P$3") (pinfunction "P$3_P$3") (pintype "bidirectional"))
      (node (ref "VCC4") (pin "P$4") (pinfunction "P$4_P$4") (pintype "bidirectional"))
      (node (ref "VCC4") (pin "P$5") (pinfunction "P$5_P$5") (pintype "bidirectional"))
      (node (ref "VCC4") (pin "P$6") (pinfunction "P$6_P$6") (pintype "bidirectional"))
      (node (ref "VCC4") (pin "P$7") (pinfunction "P$7_P$7") (pintype "bidirectional"))
      (node (ref "VCC4") (pin "P$8") (pinfunction "P$8_P$8") (pintype "bidirectional"))
      (node (ref "VCC4") (pin "P$9") (pinfunction "P$9_P$9") (pintype "bidirectional"))
      (node (ref "VCC5") (pin "P$1") (pinfunction "P$1_P$1") (pintype "bidirectional"))
      (node (ref "VCC5") (pin "P$10") (pinfunction "P$10_P$10") (pintype "bidirectional"))
      (node (ref "VCC5") (pin "P$2") (pinfunction "P$2_P$2") (pintype "bidirectional"))
      (node (ref "VCC5") (pin "P$3") (pinfunction "P$3_P$3") (pintype "bidirectional"))
      (node (ref "VCC5") (pin "P$4") (pinfunction "P$4_P$4") (pintype "bidirectional"))
      (node (ref "VCC5") (pin "P$5") (pinfunction "P$5_P$5") (pintype "bidirectional"))
      (node (ref "VCC5") (pin "P$6") (pinfunction "P$6_P$6") (pintype "bidirectional"))
      (node (ref "VCC5") (pin "P$7") (pinfunction "P$7_P$7") (pintype "bidirectional"))
      (node (ref "VCC5") (pin "P$8") (pinfunction "P$8_P$8") (pintype "bidirectional"))
      (node (ref "VCC5") (pin "P$9") (pinfunction "P$9_P$9") (pintype "bidirectional"))
    )
    (net (code "9") (name "Net-(R1-1)") (class "Default")
      (node (ref "POWER") (pin "A") (pinfunction "A_A") (pintype "passive"))
      (node (ref "R1") (pin "P$1") (pinfunction "1_P$1") (pintype "passive"))
    )
    (net (code "10") (name "Net-(R2-1)") (class "Default")
      (node (ref "POWER1") (pin "A") (pinfunction "A_A") (pintype "passive"))
      (node (ref "R2") (pin "P$1") (pinfunction "1_P$1") (pintype "passive"))
    )
    (net (code "11") (name "Net-(R2-2)") (class "Default")
      (node (ref "P1") (pin "1") (pinfunction "1_1") (pintype "passive"))
      (node (ref "R2") (pin "P$2") (pinfunction "2_P$2") (pintype "passive"))
    )
    (net (code "12") (name "Net-(R3-1)") (class "Default")
      (node (ref "POWER2") (pin "A") (pinfunction "A_A") (pintype "passive"))
      (node (ref "R3") (pin "P$1") (pinfunction "1_P$1") (pintype "passive"))
    )
    (net (code "13") (name "Net-(R4-1)") (class "Default")
      (node (ref "POWER3") (pin "A") (pinfunction "A_A") (pintype "passive"))
      (node (ref "R4") (pin "P$1") (pinfunction "1_P$1") (pintype "passive"))
    )
    (net (code "14") (name "Net-(R4-2)") (class "Default")
      (node (ref "P2") (pin "1") (pinfunction "1_1") (pintype "passive"))
      (node (ref "R4") (pin "P$2") (pinfunction "2_P$2") (pintype "passive"))
    )
    (net (code "15") (name "Net-(R5-1)") (class "Default")
      (node (ref "POWER4") (pin "A") (pinfunction "A_A") (pintype "passive"))
      (node (ref "R5") (pin "P$1") (pinfunction "1_P$1") (pintype "passive"))
    )
    (net (code "16") (name "Net-(R6-1)") (class "Default")
      (node (ref "POWER5") (pin "A") (pinfunction "A_A") (pintype "passive"))
      (node (ref "R6") (pin "P$1") (pinfunction "1_P$1") (pintype "passive"))
    )
    (net (code "17") (name "Net-(R6-2)") (class "Default")
      (node (ref "P3") (pin "1") (pinfunction "1_1") (pintype "passive"))
      (node (ref "R6") (pin "P$2") (pinfunction "2_P$2") (pintype "passive"))
    )
    (net (code "18") (name "Net-(R7-1)") (class "Default")
      (node (ref "POWER6") (pin "A") (pinfunction "A_A") (pintype "passive"))
      (node (ref "R7") (pin "P$1") (pinfunction "1_P$1") (pintype "passive"))
    )
    (net (code "19") (name "Net-(R8-1)") (class "Default")
      (node (ref "POWER7") (pin "A") (pinfunction "A_A") (pintype "passive"))
      (node (ref "R8") (pin "P$1") (pinfunction "1_P$1") (pintype "passive"))
    )
    (net (code "20") (name "Net-(R8-2)") (class "Default")
      (node (ref "P4") (pin "1") (pinfunction "1_1") (pintype "passive"))
      (node (ref "R8") (pin "P$2") (pinfunction "2_P$2") (pintype "passive"))
    )
    (net (code "21") (name "Net-(R9-1)") (class "Default")
      (node (ref "POWER8") (pin "A") (pinfunction "A_A") (pintype "passive"))
      (node (ref "R9") (pin "P$1") (pinfunction "1_P$1") (pintype "passive"))
    )
    (net (code "22") (name "Net-(R10-1)") (class "Default")
      (node (ref "POWER9") (pin "A") (pinfunction "A_A") (pintype "passive"))
      (node (ref "R10") (pin "P$1") (pinfunction "1_P$1") (pintype "passive"))
    )
    (net (code "23") (name "Net-(R10-2)") (class "Default")
      (node (ref "P5") (pin "1") (pinfunction "1_1") (pintype "passive"))
      (node (ref "R10") (pin "P$2") (pinfunction "2_P$2") (pintype "passive"))
    )
    (net (code "24") (name "Net-(R11-1)") (class "Default")
      (node (ref "POWER10") (pin "A") (pinfunction "A_A") (pintype "passive"))
      (node (ref "R11") (pin "P$1") (pinfunction "1_P$1") (pintype "passive"))
    )
    (net (code "25") (name "Net-(R12-1)") (class "Default")
      (node (ref "POWER11") (pin "A") (pinfunction "A_A") (pintype "passive"))
      (node (ref "R12") (pin "P$1") (pinfunction "1_P$1") (pintype "passive"))
    )
    (net (code "26") (name "Net-(R12-2)") (class "Default")
      (node (ref "P6") (pin "1") (pinfunction "1_1") (pintype "passive"))
      (node (ref "R12") (pin "P$2") (pinfunction "2_P$2") (pintype "passive"))
    )
  )
)
